# Lichtschranke_ArduinoBoard.net
KiCad netlist of a schematic drawn in EAGLE
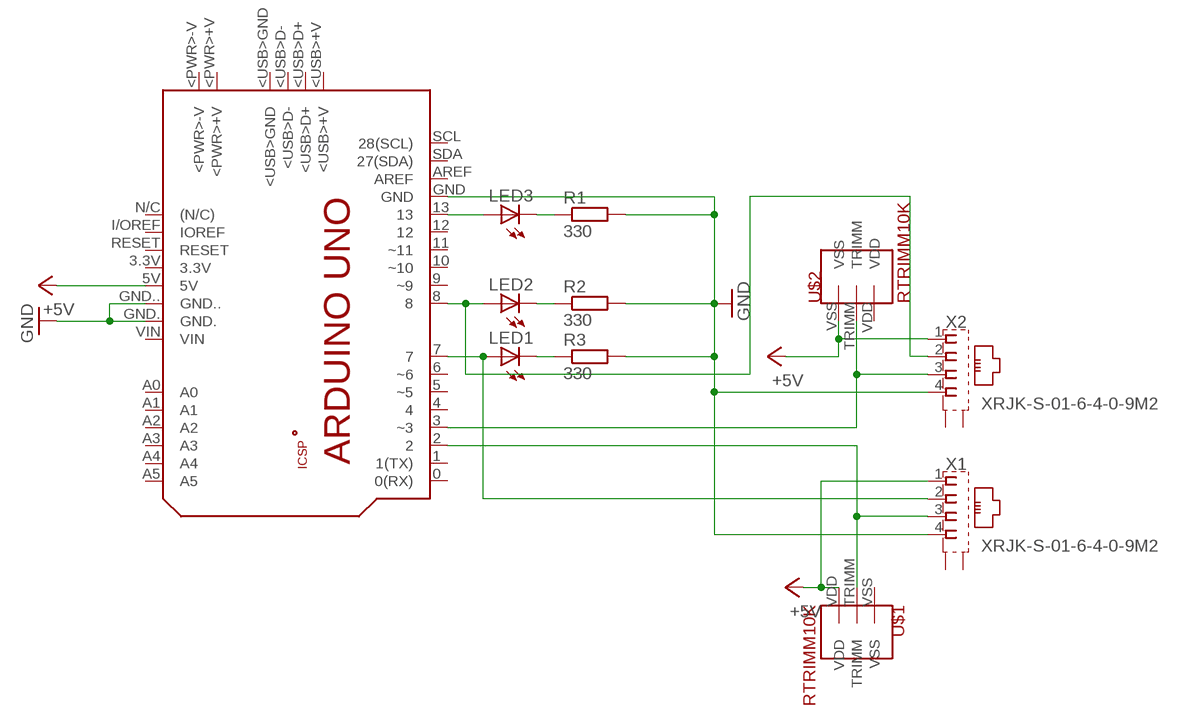
[diagram p0: schematic, sheet 1]

(export (version "E")
  (design (tool "Eeschema 10.0.6"))
  (components
    (comp (ref "LED1")
      (value "LED5MM")
      (footprint "eagle-import:LED5MM")
      (libsource (lib "eagle-import") (part "LED5MM"))
    )
    (comp (ref "LED2")
      (value "LED5MM")
      (footprint "eagle-import:LED5MM")
      (libsource (lib "eagle-import") (part "LED5MM"))
    )
    (comp (ref "LED3")
      (value "LED5MM")
      (footprint "eagle-import:LED5MM")
      (libsource (lib "eagle-import") (part "LED5MM"))
    )
    (comp (ref "PCB1")
      (value "ARDUINO_UNO")
      (footprint "eagle-import:ARDUINO_UNO")
      (libsource (lib "eagle-import") (part "ARDUINO_UNO"))
    )
    (comp (ref "R1")
      (value "330")
      (footprint "eagle-import:0411_12")
      (libsource (lib "eagle-import") (part "R-EU_0411/12"))
    )
    (comp (ref "R2")
      (value "330")
      (footprint "eagle-import:0411_12")
      (libsource (lib "eagle-import") (part "R-EU_0411/12"))
    )
    (comp (ref "R3")
      (value "330")
      (footprint "eagle-import:0411_12")
      (libsource (lib "eagle-import") (part "R-EU_0411/12"))
    )
    (comp (ref "U$1")
      (value "RTRIMM10K")
      (footprint "eagle-import:RTRIMM10K")
      (libsource (lib "eagle-import") (part "RTRIMM10K"))
    )
    (comp (ref "U$2")
      (value "RTRIMM10K")
      (footprint "eagle-import:RTRIMM10K")
      (libsource (lib "eagle-import") (part "RTRIMM10K"))
    )
    (comp (ref "X1")
      (value "XRJK-S-01-6-4-0-9M2")
      (footprint "eagle-import:XRJK-S-01-6-4-0-9M2")
      (libsource (lib "eagle-import") (part "XRJK4-0-9M2-S-01-6-"))
    )
    (comp (ref "X2")
      (value "XRJK-S-01-6-4-0-9M2")
      (footprint "eagle-import:XRJK-S-01-6-4-0-9M2")
      (libsource (lib "eagle-import") (part "XRJK4-0-9M2-S-01-6-"))
    )
  )
  (nets
    (net (code "1") (name "+5V") (class "Default")
      (node (ref "PCB1") (pin "5V") (pinfunction "5V_5V") (pintype "bidirectional"))
      (node (ref "U$1") (pin "VDD") (pinfunction "VDD_VDD") (pintype "bidirectional"))
      (node (ref "U$2") (pin "VSS") (pinfunction "VSS_VSS") (pintype "bidirectional"))
      (node (ref "X1") (pin "1") (pinfunction "1_1") (pintype "passive"))
      (node (ref "X2") (pin "1") (pinfunction "1_1") (pintype "passive"))
    )
    (net (code "2") (name "GND") (class "Default")
      (node (ref "PCB1") (pin "GND") (pinfunction "GND_GND") (pintype "bidirectional"))
      (node (ref "PCB1") (pin "GND.") (pinfunction "GND._GND.") (pintype "bidirectional"))
      (node (ref "PCB1") (pin "GND..") (pinfunction "GND.._GND..") (pintype "bidirectional"))
      (node (ref "R1") (pin "2") (pinfunction "2_2") (pintype "passive"))
      (node (ref "R2") (pin "2") (pinfunction "2_2") (pintype "passive"))
      (node (ref "R3") (pin "2") (pinfunction "2_2") (pintype "passive"))
      (node (ref "X1") (pin "4") (pinfunction "4_4") (pintype "passive"))
      (node (ref "X2") (pin "4") (pinfunction "4_4") (pintype "passive"))
    )
    (net (code "3") (name "Net-(LED1-C)") (class "Default")
      (node (ref "LED1") (pin "K") (pinfunction "C_K") (pintype "passive"))
      (node (ref "R3") (pin "1") (pinfunction "1_1") (pintype "passive"))
    )
    (net (code "4") (name "Net-(LED1-PadA)") (class "Default")
      (node (ref "LED1") (pin "A") (pinfunction "A_A") (pintype "passive"))
      (node (ref "PCB1") (pin "7") (pinfunction "7_7") (pintype "bidirectional"))
      (node (ref "X1") (pin "2") (pinfunction "2_2") (pintype "passive"))
    )
    (net (code "5") (name "Net-(LED2-C)") (class "Default")
      (node (ref "LED2") (pin "K") (pinfunction "C_K") (pintype "passive"))
      (node (ref "R2") (pin "1") (pinfunction "1_1") (pintype "passive"))
    )
    (net (code "6") (name "Net-(LED2-PadA)") (class "Default")
      (node (ref "LED2") (pin "A") (pinfunction "A_A") (pintype "passive"))
      (node (ref "PCB1") (pin "8") (pinfunction "8_8") (pintype "bidirectional"))
      (node (ref "X2") (pin "2") (pinfunction "2_2") (pintype "passive"))
    )
    (net (code "7") (name "Net-(LED3-C)") (class "Default")
      (node (ref "LED3") (pin "K") (pinfunction "C_K") (pintype "passive"))
      (node (ref "R1") (pin "1") (pinfunction "1_1") (pintype "passive"))
    )
    (net (code "8") (name "Net-(LED3-PadA)") (class "Default")
      (node (ref "LED3") (pin "A") (pinfunction "A_A") (pintype "passive"))
      (node (ref "PCB1") (pin "13") (pinfunction "13_13") (pintype "bidirectional"))
    )
    (net (code "9") (name "Net-(PCB1-Pad2)") (class "Default")
      (node (ref "PCB1") (pin "2") (pinfunction "2_2") (pintype "bidirectional"))
      (node (ref "U$1") (pin "TRIMM") (pinfunction "TRIMM_TRIMM") (pintype "bidirectional"))
      (node (ref "X1") (pin "3") (pinfunction "3_3") (pintype "passive"))
    )
    (net (code "10") (name "Net-(PCB1-~{3})") (class "Default")
      (node (ref "PCB1") (pin "3") (pinfunction "~{3}_3") (pintype "bidirectional"))
      (node (ref "U$2") (pin "TRIMM") (pinfunction "TRIMM_TRIMM") (pintype "bidirectional"))
      (node (ref "X2") (pin "3") (pinfunction "3_3") (pintype "passive"))
    )
    (net (code "11") (name "unconnected-(PCB1-(N{slash}C)-PadN{slash}C)") (class "Default")
      (node (ref "PCB1") (pin "N/C") (pinfunction "(N/C)_N/C") (pintype "bidirectional"))
    )
    (net (code "12") (name "unconnected-(PCB1-0(RX)-Pad0)") (class "Default")
      (node (ref "PCB1") (pin "0") (pinfunction "0(RX)_0") (pintype "bidirectional"))
    )
    (net (code "13") (name "unconnected-(PCB1-1(TX)-Pad1)") (class "Default")
      (node (ref "PCB1") (pin "1") (pinfunction "1(TX)_1") (pintype "bidirectional"))
    )
    (net (code "14") (name "unconnected-(PCB1-27(SDA)-PadSDA)") (class "Default")
      (node (ref "PCB1") (pin "SDA") (pinfunction "27(SDA)_SDA") (pintype "bidirectional"))
    )
    (net (code "15") (name "unconnected-(PCB1-28(SCL)-PadSCL)") (class "Default")
      (node (ref "PCB1") (pin "SCL") (pinfunction "28(SCL)_SCL") (pintype "bidirectional"))
    )
    (net (code "16") (name "unconnected-(PCB1-IOREF-PadI{slash}OREF)") (class "Default")
      (node (ref "PCB1") (pin "I/OREF") (pinfunction "IOREF_I/OREF") (pintype "bidirectional"))
    )
    (net (code "17") (name "unconnected-(PCB1-Pad+5V)") (class "Default")
      (node (ref "PCB1") (pin "+5V") (pinfunction "+5V_+5V") (pintype "bidirectional"))
    )
    (net (code "18") (name "unconnected-(PCB1-Pad3.3V)") (class "Default")
      (node (ref "PCB1") (pin "3.3V") (pinfunction "3.3V_3.3V") (pintype "bidirectional"))
    )
    (net (code "19") (name "unconnected-(PCB1-Pad4)") (class "Default")
      (node (ref "PCB1") (pin "4") (pinfunction "4_4") (pintype "bidirectional"))
    )
    (net (code "20") (name "unconnected-(PCB1-Pad12)") (class "Default")
      (node (ref "PCB1") (pin "12") (pinfunction "12_12") (pintype "bidirectional"))
    )
    (net (code "21") (name "unconnected-(PCB1-Pad<PWR>+V)") (class "Default")
      (node (ref "PCB1") (pin "<PWR>+V") (pinfunction "<PWR>+V_<PWR>+V") (pintype "bidirectional"))
    )
    (net (code "22") (name "unconnected-(PCB1-Pad<PWR>-V)") (class "Default")
      (node (ref "PCB1") (pin "<PWR>-V") (pinfunction "<PWR>-V_<PWR>-V") (pintype "bidirectional"))
    )
    (net (code "23") (name "unconnected-(PCB1-Pad<USB>+V)") (class "Default")
      (node (ref "PCB1") (pin "<USB>+V") (pinfunction "<USB>+V_<USB>+V") (pintype "bidirectional"))
    )
    (net (code "24") (name "unconnected-(PCB1-Pad<USB>D+)") (class "Default")
      (node (ref "PCB1") (pin "<USB>D+") (pinfunction "<USB>D+_<USB>D+") (pintype "bidirectional"))
    )
    (net (code "25") (name "unconnected-(PCB1-Pad<USB>D-)") (class "Default")
      (node (ref "PCB1") (pin "<USB>D-") (pinfunction "<USB>D-_<USB>D-") (pintype "bidirectional"))
    )
    (net (code "26") (name "unconnected-(PCB1-Pad<USB>GND)") (class "Default")
      (node (ref "PCB1") (pin "<USB>GND") (pinfunction "<USB>GND_<USB>GND") (pintype "bidirectional"))
    )
    (net (code "27") (name "unconnected-(PCB1-PadA0)") (class "Default")
      (node (ref "PCB1") (pin "A0") (pinfunction "A0_A0") (pintype "bidirectional"))
    )
    (net (code "28") (name "unconnected-(PCB1-PadA1)") (class "Default")
      (node (ref "PCB1") (pin "A1") (pinfunction "A1_A1") (pintype "bidirectional"))
    )
    (net (code "29") (name "unconnected-(PCB1-PadA2)") (class "Default")
      (node (ref "PCB1") (pin "A2") (pinfunction "A2_A2") (pintype "bidirectional"))
    )
    (net (code "30") (name "unconnected-(PCB1-PadA3)") (class "Default")
      (node (ref "PCB1") (pin "A3") (pinfunction "A3_A3") (pintype "bidirectional"))
    )
    (net (code "31") (name "unconnected-(PCB1-PadA4)") (class "Default")
      (node (ref "PCB1") (pin "A4") (pinfunction "A4_A4") (pintype "bidirectional"))
    )
    (net (code "32") (name "unconnected-(PCB1-PadA5)") (class "Default")
      (node (ref "PCB1") (pin "A5") (pinfunction "A5_A5") (pintype "bidirectional"))
    )
    (net (code "33") (name "unconnected-(PCB1-PadAREF)") (class "Default")
      (node (ref "PCB1") (pin "AREF") (pinfunction "AREF_AREF") (pintype "bidirectional"))
    )
    (net (code "34") (name "unconnected-(PCB1-PadGND_)") (class "Default")
      (node (ref "PCB1") (pin "GND_") (pinfunction "GND__GND_") (pintype "bidirectional"))
    )
    (net (code "35") (name "unconnected-(PCB1-PadMISO)") (class "Default")
      (node (ref "PCB1") (pin "MISO") (pinfunction "MISO_MISO") (pintype "bidirectional"))
    )
    (net (code "36") (name "unconnected-(PCB1-PadMOSI)") (class "Default")
      (node (ref "PCB1") (pin "MOSI") (pinfunction "MOSI_MOSI") (pintype "bidirectional"))
    )
    (net (code "37") (name "unconnected-(PCB1-PadRESET)") (class "Default")
      (node (ref "PCB1") (pin "RESET") (pinfunction "RESET_RESET") (pintype "bidirectional"))
    )
    (net (code "38") (name "unconnected-(PCB1-PadRESET.)") (class "Default")
      (node (ref "PCB1") (pin "RESET.") (pinfunction "RESET._RESET.") (pintype "bidirectional"))
    )
    (net (code "39") (name "unconnected-(PCB1-PadSCK)") (class "Default")
      (node (ref "PCB1") (pin "SCK") (pinfunction "SCK_SCK") (pintype "bidirectional"))
    )
    (net (code "40") (name "unconnected-(PCB1-PadVIN)") (class "Default")
      (node (ref "PCB1") (pin "VIN") (pinfunction "VIN_VIN") (pintype "bidirectional"))
    )
    (net (code "41") (name "unconnected-(PCB1-~{5}-Pad5)") (class "Default")
      (node (ref "PCB1") (pin "5") (pinfunction "~{5}_5") (pintype "bidirectional"))
    )
    (net (code "42") (name "unconnected-(PCB1-~{6}-Pad6)") (class "Default")
      (node (ref "PCB1") (pin "6") (pinfunction "~{6}_6") (pintype "bidirectional"))
    )
    (net (code "43") (name "unconnected-(PCB1-~{9}-Pad9)") (class "Default")
      (node (ref "PCB1") (pin "9") (pinfunction "~{9}_9") (pintype "bidirectional"))
    )
    (net (code "44") (name "unconnected-(PCB1-~{10}-Pad10)") (class "Default")
      (node (ref "PCB1") (pin "10") (pinfunction "~{10}_10") (pintype "bidirectional"))
    )
    (net (code "45") (name "unconnected-(PCB1-~{11}-Pad11)") (class "Default")
      (node (ref "PCB1") (pin "11") (pinfunction "~{11}_11") (pintype "bidirectional"))
    )
    (net (code "46") (name "unconnected-(U$1-PadVSS)") (class "Default")
      (node (ref "U$1") (pin "VSS") (pinfunction "VSS_VSS") (pintype "bidirectional"))
    )
    (net (code "47") (name "unconnected-(U$2-PadVDD)") (class "Default")
      (node (ref "U$2") (pin "VDD") (pinfunction "VDD_VDD") (pintype "bidirectional"))
    )
    (net (code "48") (name "unconnected-(X1-S-PadS1)") (class "Default")
      (node (ref "X1") (pin "S1") (pinfunction "S_S1") (pintype "passive"))
    )
    (net (code "49") (name "unconnected-(X1-S-PadS2)") (class "Default")
      (node (ref "X1") (pin "S2") (pinfunction "S_S2") (pintype "passive"))
    )
    (net (code "50") (name "unconnected-(X2-S-PadS1)") (class "Default")
      (node (ref "X2") (pin "S1") (pinfunction "S_S1") (pintype "passive"))
    )
    (net (code "51") (name "unconnected-(X2-S-PadS2)") (class "Default")
      (node (ref "X2") (pin "S2") (pinfunction "S_S2") (pintype "passive"))
    )
  )
)
